# Hexapod_Controller_Rev1.net
KiCad netlist of a schematic drawn in EAGLE
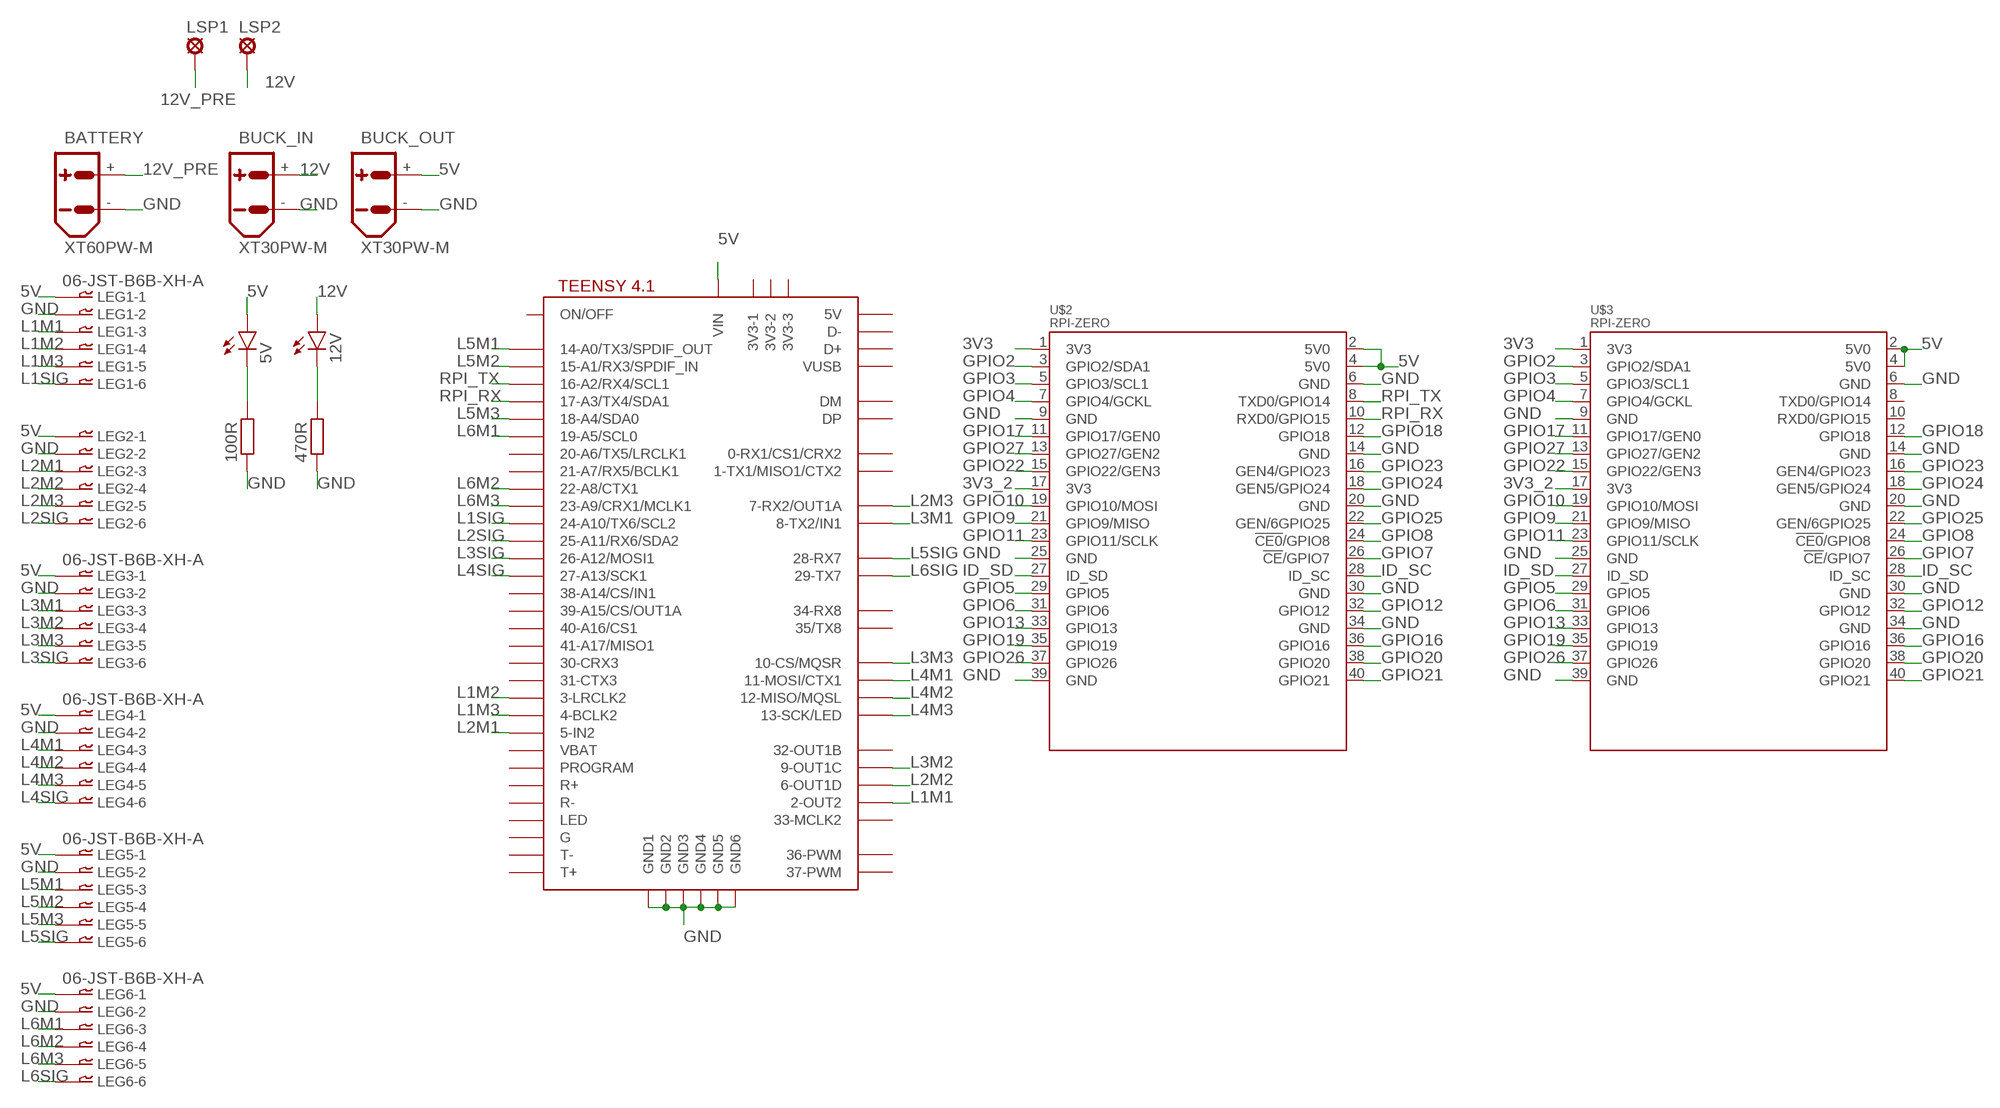
[diagram p0: schematic, sheet 1]

(export (version "E")
  (design (tool "Eeschema 10.0.6"))
  (components
    (comp (ref "5V")
      (value "LEDCHIPLED_0805")
      (footprint "eagle-import:CHIPLED_0805")
      (libsource (lib "eagle-import") (part "LEDCHIPLED_0805"))
    )
    (comp (ref "12V")
      (value "LEDCHIPLED_0805")
      (footprint "eagle-import:CHIPLED_0805")
      (libsource (lib "eagle-import") (part "LEDCHIPLED_0805"))
    )
    (comp (ref "100R")
      (value "R-EU_R0805")
      (footprint "eagle-import:R0805")
      (libsource (lib "eagle-import") (part "R-EU_R0805"))
    )
    (comp (ref "470R")
      (value "R-EU_R0805")
      (footprint "eagle-import:R0805")
      (libsource (lib "eagle-import") (part "R-EU_R0805"))
    )
    (comp (ref "BATTERY")
      (value "XT60PW-M")
      (footprint "eagle-import:XT60PW-M")
      (libsource (lib "eagle-import") (part "XT60PW-M"))
    )
    (comp (ref "BUCK_IN")
      (value "XT30PW-M")
      (footprint "eagle-import:XT30PW-M")
      (libsource (lib "eagle-import") (part "XT30PW-M"))
    )
    (comp (ref "BUCK_OUT")
      (value "XT30PW-M")
      (footprint "eagle-import:XT30PW-M")
      (libsource (lib "eagle-import") (part "XT30PW-M"))
    )
    (comp (ref "LEG1")
      (value "06-JST-B6B-XH-A")
      (footprint "eagle-import:B6B-XH")
      (libsource (lib "eagle-import") (part "06-JST-B6B-XH-A"))
    )
    (comp (ref "LEG2")
      (value "06-JST-B6B-XH-A")
      (footprint "eagle-import:B6B-XH")
      (libsource (lib "eagle-import") (part "06-JST-B6B-XH-A"))
    )
    (comp (ref "LEG3")
      (value "06-JST-B6B-XH-A")
      (footprint "eagle-import:B6B-XH")
      (libsource (lib "eagle-import") (part "06-JST-B6B-XH-A"))
    )
    (comp (ref "LEG4")
      (value "06-JST-B6B-XH-A")
      (footprint "eagle-import:B6B-XH")
      (libsource (lib "eagle-import") (part "06-JST-B6B-XH-A"))
    )
    (comp (ref "LEG5")
      (value "06-JST-B6B-XH-A")
      (footprint "eagle-import:B6B-XH")
      (libsource (lib "eagle-import") (part "06-JST-B6B-XH-A"))
    )
    (comp (ref "LEG6")
      (value "06-JST-B6B-XH-A")
      (footprint "eagle-import:B6B-XH")
      (libsource (lib "eagle-import") (part "06-JST-B6B-XH-A"))
    )
    (comp (ref "LSP1")
      (value "LSP10")
      (footprint "eagle-import:LSP10")
      (libsource (lib "eagle-import") (part "LSP10"))
    )
    (comp (ref "LSP2")
      (value "LSP10")
      (footprint "eagle-import:LSP10")
      (libsource (lib "eagle-import") (part "LSP10"))
    )
    (comp (ref "U$1")
      (value "TEENSY41")
      (footprint "eagle-import:TEENSY41")
      (libsource (lib "eagle-import") (part "TEENSY41"))
    )
    (comp (ref "U$2")
      (value "RPI-ZERO")
      (footprint "eagle-import:RASPBERRYPI_BASTELSTUBE_V13_RASPI_BOARD_B+_FULL")
      (libsource (lib "eagle-import") (part "RPI-ZERO"))
    )
    (comp (ref "U$3")
      (value "RPI-ZERO")
      (footprint "eagle-import:RASPBERRYPI_BASTELSTUBE_V13_RASPI_BOARD_B+_FULL")
      (libsource (lib "eagle-import") (part "RPI_outer_RPI-ZERO"))
    )
  )
  (nets
    (net (code "1") (name "/3V3") (class "Default")
      (node (ref "U$2") (pin "1") (pinfunction "3V3_1") (pintype "power_in"))
      (node (ref "U$3") (pin "1") (pinfunction "3V3_1") (pintype "power_in"))
    )
    (net (code "2") (name "/3V3_2") (class "Default")
      (node (ref "U$2") (pin "17") (pinfunction "3V3_17") (pintype "power_in"))
      (node (ref "U$3") (pin "17") (pinfunction "3V3_17") (pintype "power_in"))
    )
    (net (code "3") (name "/5V") (class "Default")
      (node (ref "5V") (pin "A") (pinfunction "A_A") (pintype "passive"))
      (node (ref "BUCK_OUT") (pin "+") (pinfunction "+_+") (pintype "power_in"))
      (node (ref "LEG1") (pin "P$1") (pinfunction "1_P$1") (pintype "passive"))
      (node (ref "LEG2") (pin "P$1") (pinfunction "1_P$1") (pintype "passive"))
      (node (ref "LEG3") (pin "P$1") (pinfunction "1_P$1") (pintype "passive"))
      (node (ref "LEG4") (pin "P$1") (pinfunction "1_P$1") (pintype "passive"))
      (node (ref "LEG5") (pin "P$1") (pinfunction "1_P$1") (pintype "passive"))
      (node (ref "LEG6") (pin "P$1") (pinfunction "1_P$1") (pintype "passive"))
      (node (ref "U$1") (pin "VIN") (pinfunction "VIN_VIN") (pintype "bidirectional"))
      (node (ref "U$2") (pin "2") (pinfunction "5V0_2") (pintype "power_in"))
      (node (ref "U$2") (pin "4") (pinfunction "5V0_4") (pintype "power_in"))
      (node (ref "U$3") (pin "2") (pinfunction "5V0_2") (pintype "power_in"))
      (node (ref "U$3") (pin "4") (pinfunction "5V0_4") (pintype "power_in"))
    )
    (net (code "4") (name "/12V") (class "Default")
      (node (ref "12V") (pin "A") (pinfunction "A_A") (pintype "passive"))
      (node (ref "BUCK_IN") (pin "+") (pinfunction "+_+") (pintype "power_in"))
      (node (ref "LSP2") (pin "MP") (pinfunction "MP_MP") (pintype "passive"))
    )
    (net (code "5") (name "/12V_PRE") (class "Default")
      (node (ref "BATTERY") (pin "+") (pinfunction "+_+") (pintype "power_in"))
      (node (ref "LSP1") (pin "MP") (pinfunction "MP_MP") (pintype "passive"))
    )
    (net (code "6") (name "/GND") (class "Default")
      (node (ref "100R") (pin "1") (pinfunction "1_1") (pintype "passive"))
      (node (ref "470R") (pin "1") (pinfunction "1_1") (pintype "passive"))
      (node (ref "BATTERY") (pin "-") (pinfunction "-_-") (pintype "power_in"))
      (node (ref "BUCK_IN") (pin "-") (pinfunction "-_-") (pintype "power_in"))
      (node (ref "BUCK_OUT") (pin "-") (pinfunction "-_-") (pintype "power_in"))
      (node (ref "LEG1") (pin "P$2") (pinfunction "1_P$2") (pintype "passive"))
      (node (ref "LEG2") (pin "P$2") (pinfunction "1_P$2") (pintype "passive"))
      (node (ref "LEG3") (pin "P$2") (pinfunction "1_P$2") (pintype "passive"))
      (node (ref "LEG4") (pin "P$2") (pinfunction "1_P$2") (pintype "passive"))
      (node (ref "LEG5") (pin "P$2") (pinfunction "1_P$2") (pintype "passive"))
      (node (ref "LEG6") (pin "P$2") (pinfunction "1_P$2") (pintype "passive"))
      (node (ref "U$1") (pin "GND1") (pinfunction "GND1_GND1") (pintype "bidirectional"))
      (node (ref "U$1") (pin "GND2") (pinfunction "GND2_GND2") (pintype "bidirectional"))
      (node (ref "U$1") (pin "GND3") (pinfunction "GND3_GND3") (pintype "bidirectional"))
      (node (ref "U$1") (pin "GND4") (pinfunction "GND4_GND4") (pintype "bidirectional"))
      (node (ref "U$1") (pin "GND5") (pinfunction "GND5_GND5") (pintype "bidirectional"))
      (node (ref "U$1") (pin "GND6") (pinfunction "GND6_GND6") (pintype "bidirectional"))
      (node (ref "U$2") (pin "14") (pinfunction "GND_14") (pintype "power_in"))
      (node (ref "U$2") (pin "20") (pinfunction "GND_20") (pintype "power_in"))
      (node (ref "U$2") (pin "25") (pinfunction "GND_25") (pintype "power_in"))
      (node (ref "U$2") (pin "30") (pinfunction "GND_30") (pintype "power_in"))
      (node (ref "U$2") (pin "34") (pinfunction "GND_34") (pintype "power_in"))
      (node (ref "U$2") (pin "39") (pinfunction "GND_39") (pintype "power_in"))
      (node (ref "U$2") (pin "6") (pinfunction "GND_6") (pintype "power_in"))
      (node (ref "U$2") (pin "9") (pinfunction "GND_9") (pintype "power_in"))
      (node (ref "U$3") (pin "14") (pinfunction "GND_14") (pintype "power_in"))
      (node (ref "U$3") (pin "20") (pinfunction "GND_20") (pintype "power_in"))
      (node (ref "U$3") (pin "25") (pinfunction "GND_25") (pintype "power_in"))
      (node (ref "U$3") (pin "30") (pinfunction "GND_30") (pintype "power_in"))
      (node (ref "U$3") (pin "34") (pinfunction "GND_34") (pintype "power_in"))
      (node (ref "U$3") (pin "39") (pinfunction "GND_39") (pintype "power_in"))
      (node (ref "U$3") (pin "6") (pinfunction "GND_6") (pintype "power_in"))
      (node (ref "U$3") (pin "9") (pinfunction "GND_9") (pintype "power_in"))
    )
    (net (code "7") (name "/GPIO2") (class "Default")
      (node (ref "U$2") (pin "3") (pinfunction "GPIO2/SDA1_3") (pintype "bidirectional"))
      (node (ref "U$3") (pin "3") (pinfunction "GPIO2/SDA1_3") (pintype "bidirectional"))
    )
    (net (code "8") (name "/GPIO3") (class "Default")
      (node (ref "U$2") (pin "5") (pinfunction "GPIO3/SCL1_5") (pintype "bidirectional"))
      (node (ref "U$3") (pin "5") (pinfunction "GPIO3/SCL1_5") (pintype "bidirectional"))
    )
    (net (code "9") (name "/GPIO4") (class "Default")
      (node (ref "U$2") (pin "7") (pinfunction "GPIO4/GCKL_7") (pintype "bidirectional"))
      (node (ref "U$3") (pin "7") (pinfunction "GPIO4/GCKL_7") (pintype "bidirectional"))
    )
    (net (code "10") (name "/GPIO5") (class "Default")
      (node (ref "U$2") (pin "29") (pinfunction "GPIO5_29") (pintype "bidirectional"))
      (node (ref "U$3") (pin "29") (pinfunction "GPIO5_29") (pintype "bidirectional"))
    )
    (net (code "11") (name "/GPIO6") (class "Default")
      (node (ref "U$2") (pin "31") (pinfunction "GPIO6_31") (pintype "bidirectional"))
      (node (ref "U$3") (pin "31") (pinfunction "GPIO6_31") (pintype "bidirectional"))
    )
    (net (code "12") (name "/GPIO7") (class "Default")
      (node (ref "U$2") (pin "26") (pinfunction "~{CE}/GPIO7_26") (pintype "bidirectional"))
      (node (ref "U$3") (pin "26") (pinfunction "~{CE}/GPIO7_26") (pintype "bidirectional"))
    )
    (net (code "13") (name "/GPIO8") (class "Default")
      (node (ref "U$2") (pin "24") (pinfunction "~{CE0}/GPIO8_24") (pintype "bidirectional"))
      (node (ref "U$3") (pin "24") (pinfunction "~{CE0}/GPIO8_24") (pintype "bidirectional"))
    )
    (net (code "14") (name "/GPIO9") (class "Default")
      (node (ref "U$2") (pin "21") (pinfunction "GPIO9/MISO_21") (pintype "bidirectional"))
      (node (ref "U$3") (pin "21") (pinfunction "GPIO9/MISO_21") (pintype "bidirectional"))
    )
    (net (code "15") (name "/GPIO10") (class "Default")
      (node (ref "U$2") (pin "19") (pinfunction "GPIO10/MOSI_19") (pintype "bidirectional"))
      (node (ref "U$3") (pin "19") (pinfunction "GPIO10/MOSI_19") (pintype "bidirectional"))
    )
    (net (code "16") (name "/GPIO11") (class "Default")
      (node (ref "U$2") (pin "23") (pinfunction "GPIO11/SCLK_23") (pintype "bidirectional"))
      (node (ref "U$3") (pin "23") (pinfunction "GPIO11/SCLK_23") (pintype "bidirectional"))
    )
    (net (code "17") (name "/GPIO12") (class "Default")
      (node (ref "U$2") (pin "32") (pinfunction "GPIO12_32") (pintype "bidirectional"))
      (node (ref "U$3") (pin "32") (pinfunction "GPIO12_32") (pintype "bidirectional"))
    )
    (net (code "18") (name "/GPIO13") (class "Default")
      (node (ref "U$2") (pin "33") (pinfunction "GPIO13_33") (pintype "bidirectional"))
      (node (ref "U$3") (pin "33") (pinfunction "GPIO13_33") (pintype "bidirectional"))
    )
    (net (code "19") (name "/GPIO16") (class "Default")
      (node (ref "U$2") (pin "36") (pinfunction "GPIO16_36") (pintype "bidirectional"))
      (node (ref "U$3") (pin "36") (pinfunction "GPIO16_36") (pintype "bidirectional"))
    )
    (net (code "20") (name "/GPIO17") (class "Default")
      (node (ref "U$2") (pin "11") (pinfunction "GPIO17/GEN0_11") (pintype "bidirectional"))
      (node (ref "U$3") (pin "11") (pinfunction "GPIO17/GEN0_11") (pintype "bidirectional"))
    )
    (net (code "21") (name "/GPIO18") (class "Default")
      (node (ref "U$2") (pin "12") (pinfunction "GPIO18_12") (pintype "bidirectional"))
      (node (ref "U$3") (pin "12") (pinfunction "GPIO18_12") (pintype "bidirectional"))
    )
    (net (code "22") (name "/GPIO19") (class "Default")
      (node (ref "U$2") (pin "35") (pinfunction "GPIO19_35") (pintype "bidirectional"))
      (node (ref "U$3") (pin "35") (pinfunction "GPIO19_35") (pintype "bidirectional"))
    )
    (net (code "23") (name "/GPIO20") (class "Default")
      (node (ref "U$2") (pin "38") (pinfunction "GPIO20_38") (pintype "bidirectional"))
      (node (ref "U$3") (pin "38") (pinfunction "GPIO20_38") (pintype "bidirectional"))
    )
    (net (code "24") (name "/GPIO21") (class "Default")
      (node (ref "U$2") (pin "40") (pinfunction "GPIO21_40") (pintype "bidirectional"))
      (node (ref "U$3") (pin "40") (pinfunction "GPIO21_40") (pintype "bidirectional"))
    )
    (net (code "25") (name "/GPIO22") (class "Default")
      (node (ref "U$2") (pin "15") (pinfunction "GPIO22/GEN3_15") (pintype "bidirectional"))
      (node (ref "U$3") (pin "15") (pinfunction "GPIO22/GEN3_15") (pintype "bidirectional"))
    )
    (net (code "26") (name "/GPIO23") (class "Default")
      (node (ref "U$2") (pin "16") (pinfunction "GEN4/GPIO23_16") (pintype "bidirectional"))
      (node (ref "U$3") (pin "16") (pinfunction "GEN4/GPIO23_16") (pintype "bidirectional"))
    )
    (net (code "27") (name "/GPIO24") (class "Default")
      (node (ref "U$2") (pin "18") (pinfunction "GEN5/GPIO24_18") (pintype "bidirectional"))
      (node (ref "U$3") (pin "18") (pinfunction "GEN5/GPIO24_18") (pintype "bidirectional"))
    )
    (net (code "28") (name "/GPIO25") (class "Default")
      (node (ref "U$2") (pin "22") (pinfunction "GEN/6GPIO25_22") (pintype "bidirectional"))
      (node (ref "U$3") (pin "22") (pinfunction "GEN/6GPIO25_22") (pintype "bidirectional"))
    )
    (net (code "29") (name "/GPIO26") (class "Default")
      (node (ref "U$2") (pin "37") (pinfunction "GPIO26_37") (pintype "bidirectional"))
      (node (ref "U$3") (pin "37") (pinfunction "GPIO26_37") (pintype "bidirectional"))
    )
    (net (code "30") (name "/GPIO27") (class "Default")
      (node (ref "U$2") (pin "13") (pinfunction "GPIO27/GEN2_13") (pintype "bidirectional"))
      (node (ref "U$3") (pin "13") (pinfunction "GPIO27/GEN2_13") (pintype "bidirectional"))
    )
    (net (code "31") (name "/ID_SC") (class "Default")
      (node (ref "U$2") (pin "28") (pinfunction "ID_SC_28") (pintype "bidirectional"))
      (node (ref "U$3") (pin "28") (pinfunction "ID_SC_28") (pintype "bidirectional"))
    )
    (net (code "32") (name "/ID_SD") (class "Default")
      (node (ref "U$2") (pin "27") (pinfunction "ID_SD_27") (pintype "bidirectional"))
      (node (ref "U$3") (pin "27") (pinfunction "ID_SD_27") (pintype "bidirectional"))
    )
    (net (code "33") (name "/L1M1") (class "Default")
      (node (ref "LEG1") (pin "P$3") (pinfunction "1_P$3") (pintype "passive"))
      (node (ref "U$1") (pin "2-OUT2") (pinfunction "2-OUT2_2-OUT2") (pintype "bidirectional"))
    )
    (net (code "34") (name "/L1M2") (class "Default")
      (node (ref "LEG1") (pin "P$4") (pinfunction "1_P$4") (pintype "passive"))
      (node (ref "U$1") (pin "3-LRCLK2") (pinfunction "3-LRCLK2_3-LRCLK2") (pintype "bidirectional"))
    )
    (net (code "35") (name "/L1M3") (class "Default")
      (node (ref "LEG1") (pin "P$5") (pinfunction "1_P$5") (pintype "passive"))
      (node (ref "U$1") (pin "4-BCLK2") (pinfunction "4-BCLK2_4-BCLK2") (pintype "bidirectional"))
    )
    (net (code "36") (name "/L1SIG") (class "Default")
      (node (ref "LEG1") (pin "P$6") (pinfunction "1_P$6") (pintype "passive"))
      (node (ref "U$1") (pin "24-A10/TX6/SCL2") (pinfunction "24-A10/TX6/SCL2_24-A10/TX6/SCL2") (pintype "bidirectional"))
    )
    (net (code "37") (name "/L2M1") (class "Default")
      (node (ref "LEG2") (pin "P$3") (pinfunction "1_P$3") (pintype "passive"))
      (node (ref "U$1") (pin "5-IN2") (pinfunction "5-IN2_5-IN2") (pintype "bidirectional"))
    )
    (net (code "38") (name "/L2M2") (class "Default")
      (node (ref "LEG2") (pin "P$4") (pinfunction "1_P$4") (pintype "passive"))
      (node (ref "U$1") (pin "6-OUT1D") (pinfunction "6-OUT1D_6-OUT1D") (pintype "bidirectional"))
    )
    (net (code "39") (name "/L2M3") (class "Default")
      (node (ref "LEG2") (pin "P$5") (pinfunction "1_P$5") (pintype "passive"))
      (node (ref "U$1") (pin "7-RX2/OUT1A") (pinfunction "7-RX2/OUT1A_7-RX2/OUT1A") (pintype "bidirectional"))
    )
    (net (code "40") (name "/L2SIG") (class "Default")
      (node (ref "LEG2") (pin "P$6") (pinfunction "1_P$6") (pintype "passive"))
      (node (ref "U$1") (pin "25-A11/RX6/SDA2") (pinfunction "25-A11/RX6/SDA2_25-A11/RX6/SDA2") (pintype "bidirectional"))
    )
    (net (code "41") (name "/L3M1") (class "Default")
      (node (ref "LEG3") (pin "P$3") (pinfunction "1_P$3") (pintype "passive"))
      (node (ref "U$1") (pin "8-TX2/IN2") (pinfunction "8-TX2/IN1_8-TX2/IN2") (pintype "bidirectional"))
    )
    (net (code "42") (name "/L3M2") (class "Default")
      (node (ref "LEG3") (pin "P$4") (pinfunction "1_P$4") (pintype "passive"))
      (node (ref "U$1") (pin "9-OUT1C") (pinfunction "9-OUT1C_9-OUT1C") (pintype "bidirectional"))
    )
    (net (code "43") (name "/L3M3") (class "Default")
      (node (ref "LEG3") (pin "P$5") (pinfunction "1_P$5") (pintype "passive"))
      (node (ref "U$1") (pin "10-CS\\MQSR") (pinfunction "10-CS/MQSR_10-CS\\MQSR") (pintype "bidirectional"))
    )
    (net (code "44") (name "/L3SIG") (class "Default")
      (node (ref "LEG3") (pin "P$6") (pinfunction "1_P$6") (pintype "passive"))
      (node (ref "U$1") (pin "26-A12/MOSI1") (pinfunction "26-A12/MOSI1_26-A12/MOSI1") (pintype "bidirectional"))
    )
    (net (code "45") (name "/L4M1") (class "Default")
      (node (ref "LEG4") (pin "P$3") (pinfunction "1_P$3") (pintype "passive"))
      (node (ref "U$1") (pin "11-MOSI/CTX1") (pinfunction "11-MOSI/CTX1_11-MOSI/CTX1") (pintype "bidirectional"))
    )
    (net (code "46") (name "/L4M2") (class "Default")
      (node (ref "LEG4") (pin "P$4") (pinfunction "1_P$4") (pintype "passive"))
      (node (ref "U$1") (pin "12-MISO/MQSL") (pinfunction "12-MISO/MQSL_12-MISO/MQSL") (pintype "bidirectional"))
    )
    (net (code "47") (name "/L4M3") (class "Default")
      (node (ref "LEG4") (pin "P$5") (pinfunction "1_P$5") (pintype "passive"))
      (node (ref "U$1") (pin "13-SCK/LED") (pinfunction "13-SCK/LED_13-SCK/LED") (pintype "bidirectional"))
    )
    (net (code "48") (name "/L4SIG") (class "Default")
      (node (ref "LEG4") (pin "P$6") (pinfunction "1_P$6") (pintype "passive"))
      (node (ref "U$1") (pin "27-A13/SCK1") (pinfunction "27-A13/SCK1_27-A13/SCK1") (pintype "bidirectional"))
    )
    (net (code "49") (name "/L5M1") (class "Default")
      (node (ref "LEG5") (pin "P$3") (pinfunction "1_P$3") (pintype "passive"))
      (node (ref "U$1") (pin "14-A0/TX3/SPDIF_OUT") (pinfunction "14-A0/TX3/SPDIF_OUT_14-A0/TX3/SPDIF_OUT") (pintype "bidirectional"))
    )
    (net (code "50") (name "/L5M2") (class "Default")
      (node (ref "LEG5") (pin "P$4") (pinfunction "1_P$4") (pintype "passive"))
      (node (ref "U$1") (pin "15-A1/RX3/SPDIF_IN") (pinfunction "15-A1/RX3/SPDIF_IN_15-A1/RX3/SPDIF_IN") (pintype "bidirectional"))
    )
    (net (code "51") (name "/L5M3") (class "Default")
      (node (ref "LEG5") (pin "P$5") (pinfunction "1_P$5") (pintype "passive"))
      (node (ref "U$1") (pin "18-A4/SDA0") (pinfunction "18-A4/SDA0_18-A4/SDA0") (pintype "bidirectional"))
    )
    (net (code "52") (name "/L5SIG") (class "Default")
      (node (ref "LEG5") (pin "P$6") (pinfunction "1_P$6") (pintype "passive"))
      (node (ref "U$1") (pin "28-RX7") (pinfunction "28-RX7_28-RX7") (pintype "bidirectional"))
    )
    (net (code "53") (name "/L6M1") (class "Default")
      (node (ref "LEG6") (pin "P$3") (pinfunction "1_P$3") (pintype "passive"))
      (node (ref "U$1") (pin "19-A5/SCL0") (pinfunction "19-A5/SCL0_19-A5/SCL0") (pintype "bidirectional"))
    )
    (net (code "54") (name "/L6M2") (class "Default")
      (node (ref "LEG6") (pin "P$4") (pinfunction "1_P$4") (pintype "passive"))
      (node (ref "U$1") (pin "22-A8/CTX1") (pinfunction "22-A8/CTX1_22-A8/CTX1") (pintype "bidirectional"))
    )
    (net (code "55") (name "/L6M3") (class "Default")
      (node (ref "LEG6") (pin "P$5") (pinfunction "1_P$5") (pintype "passive"))
      (node (ref "U$1") (pin "23-A9/CRX1/MCLK1") (pinfunction "23-A9/CRX1/MCLK1_23-A9/CRX1/MCLK1") (pintype "bidirectional"))
    )
    (net (code "56") (name "/L6SIG") (class "Default")
      (node (ref "LEG6") (pin "P$6") (pinfunction "1_P$6") (pintype "passive"))
      (node (ref "U$1") (pin "29-TX7") (pinfunction "29-TX7_29-TX7") (pintype "bidirectional"))
    )
    (net (code "57") (name "/RPI_RX") (class "Default")
      (node (ref "U$1") (pin "17-A3/TX4/SDA1") (pinfunction "17-A3/TX4/SDA1_17-A3/TX4/SDA1") (pintype "bidirectional"))
      (node (ref "U$2") (pin "10") (pinfunction "RXD0/GPIO15_10") (pintype "bidirectional"))
    )
    (net (code "58") (name "/RPI_TX") (class "Default")
      (node (ref "U$1") (pin "16-A2/RX4/SCL1") (pinfunction "16-A2/RX4/SCL1_16-A2/RX4/SCL1") (pintype "bidirectional"))
      (node (ref "U$2") (pin "8") (pinfunction "TXD0/GPIO14_8") (pintype "bidirectional"))
    )
    (net (code "59") (name "Net-(12V-PadC)") (class "Default")
      (node (ref "12V") (pin "C") (pinfunction "C_C") (pintype "passive"))
      (node (ref "470R") (pin "2") (pinfunction "2_2") (pintype "passive"))
    )
    (net (code "60") (name "Net-(100R-Pad2)") (class "Default")
      (node (ref "100R") (pin "2") (pinfunction "2_2") (pintype "passive"))
      (node (ref "5V") (pin "C") (pinfunction "C_C") (pintype "passive"))
    )
    (net (code "61") (name "unconnected-(U$1-5V-Pad+5V)") (class "Default")
      (node (ref "U$1") (pin "+5V") (pinfunction "5V_+5V") (pintype "bidirectional"))
    )
    (net (code "62") (name "unconnected-(U$1-35{slash}TX8-Pad35-TX8)") (class "Default")
      (node (ref "U$1") (pin "35-TX8") (pinfunction "35/TX8_35-TX8") (pintype "bidirectional"))
    )
    (net (code "63") (name "unconnected-(U$1-Pad0-RX1{slash}CS1{slash}CRX2)") (class "Default")
      (node (ref "U$1") (pin "0-RX1/CS1/CRX2") (pinfunction "0-RX1/CS1/CRX2_0-RX1/CS1/CRX2") (pintype "bidirectional"))
    )
    (net (code "64") (name "unconnected-(U$1-Pad1-TX1{slash}MISO1{slash}CTX2)") (class "Default")
      (node (ref "U$1") (pin "1-TX1/MISO1/CTX2") (pinfunction "1-TX1/MISO1/CTX2_1-TX1/MISO1/CTX2") (pintype "bidirectional"))
    )
    (net (code "65") (name "unconnected-(U$1-Pad3V3-1)") (class "Default")
      (node (ref "U$1") (pin "3V3-1") (pinfunction "3V3-1_3V3-1") (pintype "bidirectional"))
    )
    (net (code "66") (name "unconnected-(U$1-Pad3V3-2)") (class "Default")
      (node (ref "U$1") (pin "3V3-2") (pinfunction "3V3-2_3V3-2") (pintype "bidirectional"))
    )
    (net (code "67") (name "unconnected-(U$1-Pad3V3-3)") (class "Default")
      (node (ref "U$1") (pin "3V3-3") (pinfunction "3V3-3_3V3-3") (pintype "bidirectional"))
    )
    (net (code "68") (name "unconnected-(U$1-Pad20-A6{slash}TX5{slash}LRCLK1)") (class "Default")
      (node (ref "U$1") (pin "20-A6/TX5/LRCLK1") (pinfunction "20-A6/TX5/LRCLK1_20-A6/TX5/LRCLK1") (pintype "bidirectional"))
    )
    (net (code "69") (name "unconnected-(U$1-Pad21-A7{slash}RX5{slash}BCLK1)") (class "Default")
      (node (ref "U$1") (pin "21-A7/RX5/BCLK1") (pinfunction "21-A7/RX5/BCLK1_21-A7/RX5/BCLK1") (pintype "bidirectional"))
    )
    (net (code "70") (name "unconnected-(U$1-Pad30-CRX3)") (class "Default")
      (node (ref "U$1") (pin "30-CRX3") (pinfunction "30-CRX3_30-CRX3") (pintype "bidirectional"))
    )
    (net (code "71") (name "unconnected-(U$1-Pad31-CTX3)") (class "Default")
      (node (ref "U$1") (pin "31-CTX3") (pinfunction "31-CTX3_31-CTX3") (pintype "bidirectional"))
    )
    (net (code "72") (name "unconnected-(U$1-Pad32-OUT1B)") (class "Default")
      (node (ref "U$1") (pin "32-OUT1B") (pinfunction "32-OUT1B_32-OUT1B") (pintype "bidirectional"))
    )
    (net (code "73") (name "unconnected-(U$1-Pad33-MCLK2)") (class "Default")
      (node (ref "U$1") (pin "33-MCLK2") (pinfunction "33-MCLK2_33-MCLK2") (pintype "bidirectional"))
    )
    (net (code "74") (name "unconnected-(U$1-Pad34-RX8)") (class "Default")
      (node (ref "U$1") (pin "34-RX8") (pinfunction "34-RX8_34-RX8") (pintype "bidirectional"))
    )
    (net (code "75") (name "unconnected-(U$1-Pad36-PWM)") (class "Default")
      (node (ref "U$1") (pin "36-PWM") (pinfunction "36-PWM_36-PWM") (pintype "bidirectional"))
    )
    (net (code "76") (name "unconnected-(U$1-Pad37-PWM)") (class "Default")
      (node (ref "U$1") (pin "37-PWM") (pinfunction "37-PWM_37-PWM") (pintype "bidirectional"))
    )
    (net (code "77") (name "unconnected-(U$1-Pad38-A14{slash}CS{slash}IN1)") (class "Default")
      (node (ref "U$1") (pin "38-A14/CS/IN1") (pinfunction "38-A14/CS/IN1_38-A14/CS/IN1") (pintype "bidirectional"))
    )
    (net (code "78") (name "unconnected-(U$1-Pad39-A15{slash}CS{slash}OUT1A)") (class "Default")
      (node (ref "U$1") (pin "39-A15/CS/OUT1A") (pinfunction "39-A15/CS/OUT1A_39-A15/CS/OUT1A") (pintype "bidirectional"))
    )
    (net (code "79") (name "unconnected-(U$1-Pad40-A16{slash}CS1)") (class "Default")
      (node (ref "U$1") (pin "40-A16/CS1") (pinfunction "40-A16/CS1_40-A16/CS1") (pintype "bidirectional"))
    )
    (net (code "80") (name "unconnected-(U$1-Pad41-A17{slash}MISO1)") (class "Default")
      (node (ref "U$1") (pin "41-A17/MISO1") (pinfunction "41-A17/MISO1_41-A17/MISO1") (pintype "bidirectional"))
    )
    (net (code "81") (name "unconnected-(U$1-PadD+)") (class "Default")
      (node (ref "U$1") (pin "D+") (pinfunction "D+_D+") (pintype "bidirectional"))
    )
    (net (code "82") (name "unconnected-(U$1-PadD-)") (class "Default")
      (node (ref "U$1") (pin "D-") (pinfunction "D-_D-") (pintype "bidirectional"))
    )
    (net (code "83") (name "unconnected-(U$1-PadDM)") (class "Default")
      (node (ref "U$1") (pin "DM") (pinfunction "DM_DM") (pintype "bidirectional"))
    )
    (net (code "84") (name "unconnected-(U$1-PadDP)") (class "Default")
      (node (ref "U$1") (pin "DP") (pinfunction "DP_DP") (pintype "bidirectional"))
    )
    (net (code "85") (name "unconnected-(U$1-PadG)") (class "Default")
      (node (ref "U$1") (pin "G") (pinfunction "G_G") (pintype "bidirectional"))
    )
    (net (code "86") (name "unconnected-(U$1-PadLED)") (class "Default")
      (node (ref "U$1") (pin "LED") (pinfunction "LED_LED") (pintype "bidirectional"))
    )
    (net (code "87") (name "unconnected-(U$1-PadON{slash}OFF)") (class "Default")
      (node (ref "U$1") (pin "ON/OFF") (pinfunction "ON/OFF_ON/OFF") (pintype "bidirectional"))
    )
    (net (code "88") (name "unconnected-(U$1-PadPROGRAM)") (class "Default")
      (node (ref "U$1") (pin "PROGRAM") (pinfunction "PROGRAM_PROGRAM") (pintype "bidirectional"))
    )
    (net (code "89") (name "unconnected-(U$1-PadR+)") (class "Default")
      (node (ref "U$1") (pin "R+") (pinfunction "R+_R+") (pintype "bidirectional"))
    )
    (net (code "90") (name "unconnected-(U$1-PadR-)") (class "Default")
      (node (ref "U$1") (pin "R-") (pinfunction "R-_R-") (pintype "bidirectional"))
    )
    (net (code "91") (name "unconnected-(U$1-PadT+)") (class "Default")
      (node (ref "U$1") (pin "T+") (pinfunction "T+_T+") (pintype "bidirectional"))
    )
    (net (code "92") (name "unconnected-(U$1-PadT-)") (class "Default")
      (node (ref "U$1") (pin "T-") (pinfunction "T-_T-") (pintype "bidirectional"))
    )
    (net (code "93") (name "unconnected-(U$1-PadVBAT)") (class "Default")
      (node (ref "U$1") (pin "VBAT") (pinfunction "VBAT_VBAT") (pintype "bidirectional"))
    )
    (net (code "94") (name "unconnected-(U$1-PadVUSB)") (class "Default")
      (node (ref "U$1") (pin "VUSB") (pinfunction "VUSB_VUSB") (pintype "bidirectional"))
    )
    (net (code "95") (name "unconnected-(U$3-RXD0{slash}GPIO15-Pad10)") (class "Default")
      (node (ref "U$3") (pin "10") (pinfunction "RXD0/GPIO15_10") (pintype "bidirectional"))
    )
    (net (code "96") (name "unconnected-(U$3-TXD0{slash}GPIO14-Pad8)") (class "Default")
      (node (ref "U$3") (pin "8") (pinfunction "TXD0/GPIO14_8") (pintype "bidirectional"))
    )
  )
)
